# usb-can_v2_1.net
KiCad netlist of a schematic drawn in EAGLE
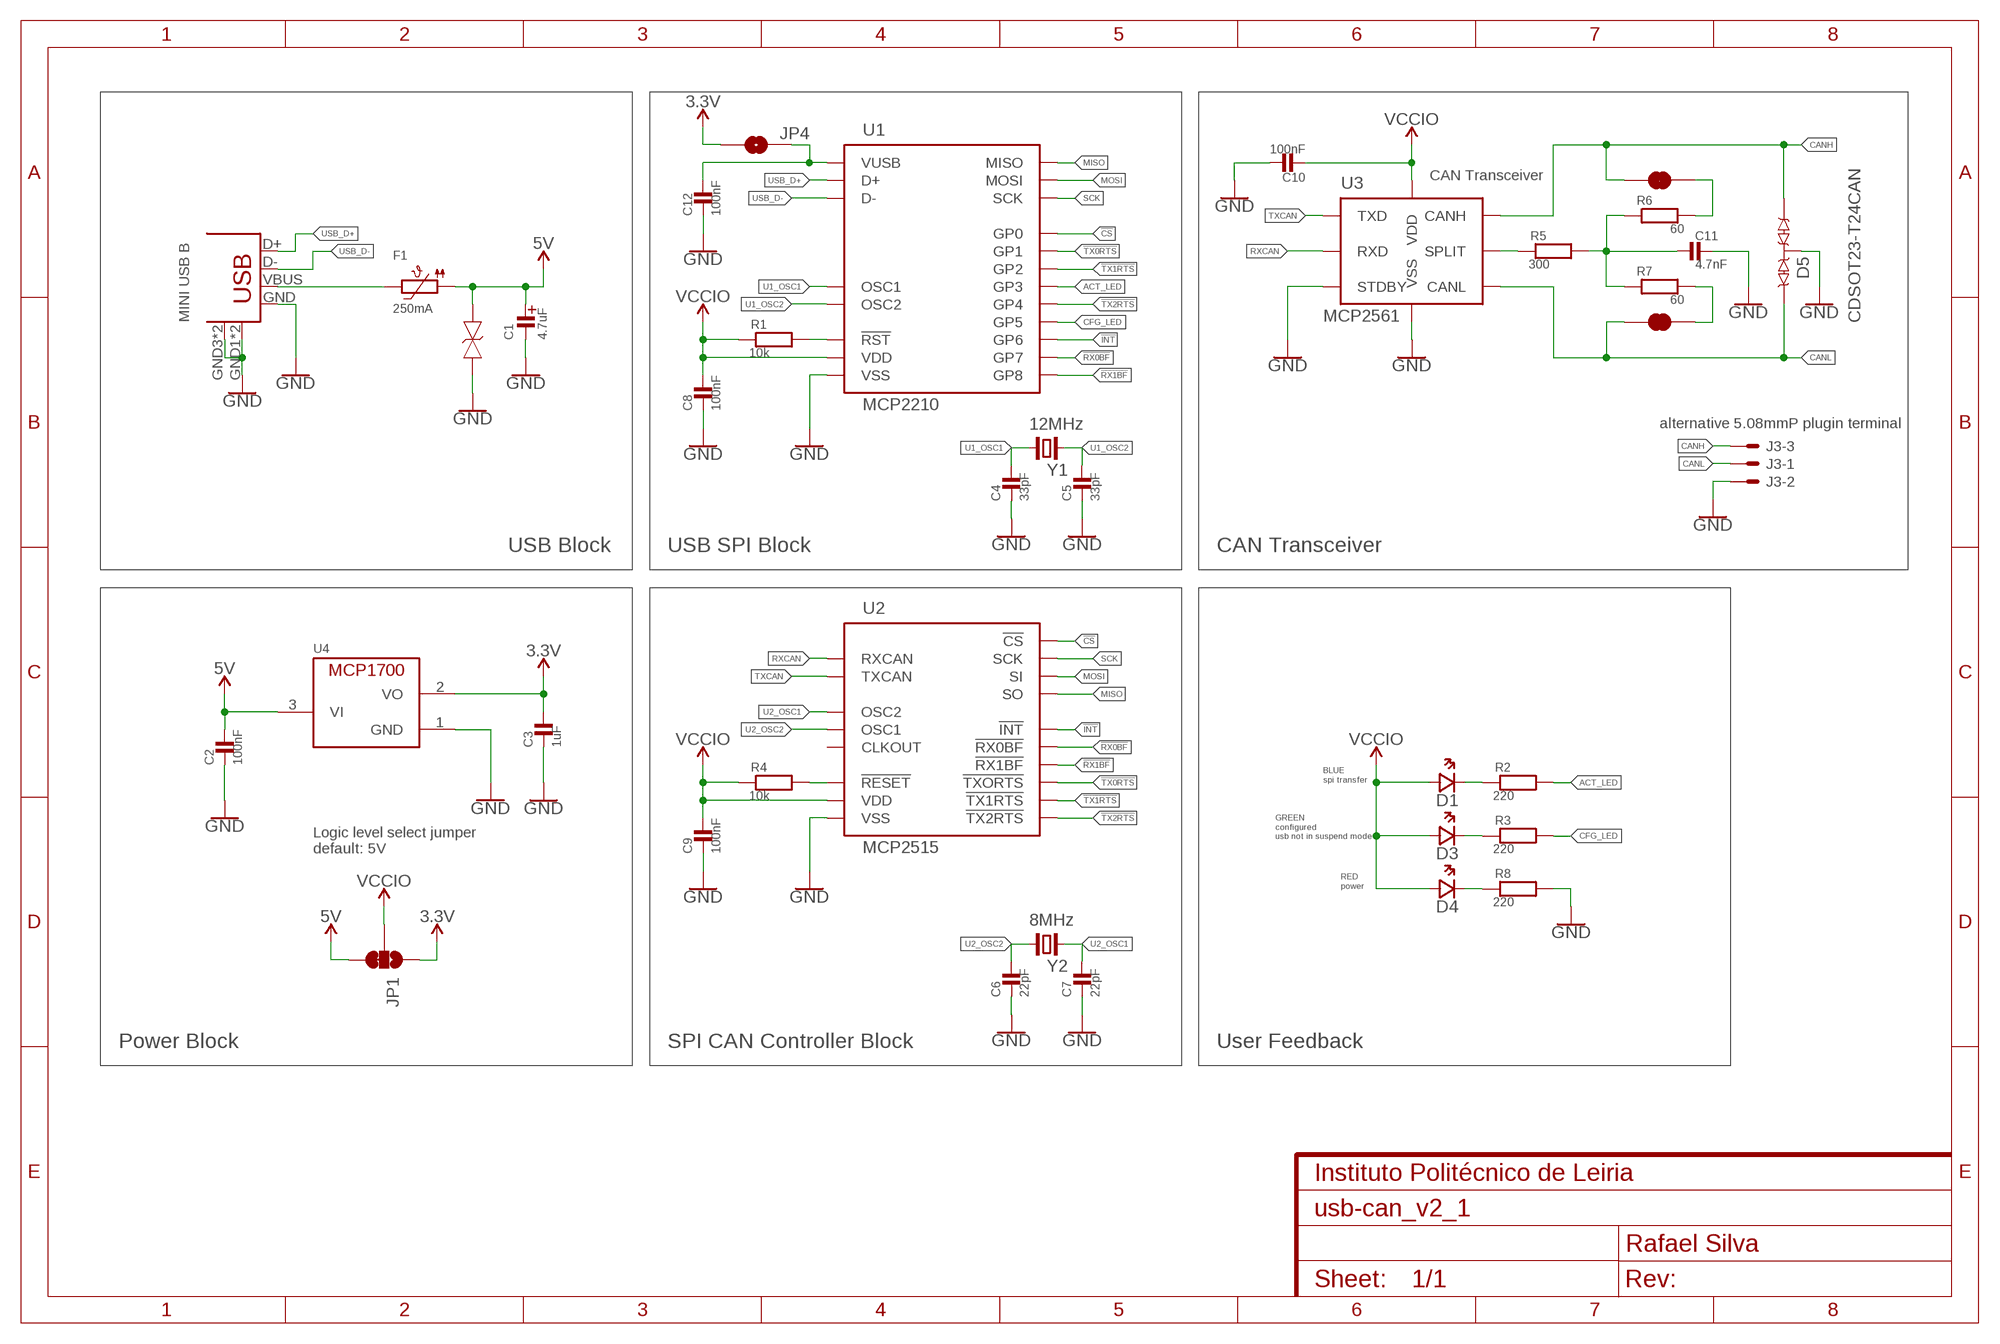
[diagram p0: schematic, sheet 1]

(export (version "E")
  (design (tool "Eeschema 10.0.6"))
  (components
    (comp (ref "C1")
      (value "4.7uF")
      (footprint "eagle-import:EIA3216")
      (libsource (lib "eagle-import") (part "CAPACITOR_TAN3216"))
    )
    (comp (ref "C2")
      (value "100nF")
      (footprint "eagle-import:0603_WAVE")
      (libsource (lib "eagle-import") (part "CAPACITOR_C0603"))
    )
    (comp (ref "C3")
      (value "1uF")
      (footprint "eagle-import:0603_WAVE")
      (libsource (lib "eagle-import") (part "CAPACITOR_C0603"))
    )
    (comp (ref "C4")
      (value "33pF")
      (footprint "eagle-import:0603_WAVE")
      (libsource (lib "eagle-import") (part "CAPACITOR_C0603"))
    )
    (comp (ref "C5")
      (value "33pF")
      (footprint "eagle-import:0603_WAVE")
      (libsource (lib "eagle-import") (part "CAPACITOR_C0603"))
    )
    (comp (ref "C6")
      (value "22pF")
      (footprint "eagle-import:0603_WAVE")
      (libsource (lib "eagle-import") (part "CAPACITOR_C0603"))
    )
    (comp (ref "C7")
      (value "22pF")
      (footprint "eagle-import:0603_WAVE")
      (libsource (lib "eagle-import") (part "CAPACITOR_C0603"))
    )
    (comp (ref "C8")
      (value "100nF")
      (footprint "eagle-import:0603_WAVE")
      (libsource (lib "eagle-import") (part "CAPACITOR_C0603"))
    )
    (comp (ref "C9")
      (value "100nF")
      (footprint "eagle-import:0603_WAVE")
      (libsource (lib "eagle-import") (part "CAPACITOR_C0603"))
    )
    (comp (ref "C10")
      (value "100nF")
      (footprint "eagle-import:0603_WAVE")
      (libsource (lib "eagle-import") (part "CAPACITOR_C0603"))
    )
    (comp (ref "C11")
      (value "4.7nF")
      (footprint "eagle-import:0603_WAVE")
      (libsource (lib "eagle-import") (part "CAPACITOR_C0603"))
    )
    (comp (ref "C12")
      (value "100nF")
      (footprint "eagle-import:0603_WAVE")
      (libsource (lib "eagle-import") (part "CAPACITOR_C0603"))
    )
    (comp (ref "D1")
      (value "Blue")
      (footprint "eagle-import:CHIPLED_0603")
      (libsource (lib "eagle-import") (part "LED0603"))
    )
    (comp (ref "D2")
      (value "PESD5V0S1BAF")
      (footprint "eagle-import:SOD323")
      (libsource (lib "eagle-import") (part "PESD5V0S1BAF"))
    )
    (comp (ref "D3")
      (value "Green")
      (footprint "eagle-import:CHIPLED_0603")
      (libsource (lib "eagle-import") (part "LED0603"))
    )
    (comp (ref "D4")
      (value "Red")
      (footprint "eagle-import:CHIPLED_0603")
      (libsource (lib "eagle-import") (part "LED0603"))
    )
    (comp (ref "D5")
      (value "CDSOT23-T24CAN")
      (footprint "eagle-import:SOT-23-3")
      (libsource (lib "eagle-import") (part "CDSOT23-T24CAN"))
    )
    (comp (ref "F1")
      (value "250mA")
      (footprint "eagle-import:_1206")
      (libsource (lib "eagle-import") (part "PTC1206"))
    )
    (comp (ref "J2")
      (value "USB_MINI_BMINIB")
      (footprint "eagle-import:USB-MINIB")
      (libsource (lib "eagle-import") (part "USB_MINI_BMINIB"))
    )
    (comp (ref "J3")
      (value "1X32EHGR")
      (footprint "eagle-import:2EHGR")
      (libsource (lib "eagle-import") (part "1X32EHGR"))
    )
    (comp (ref "JP1")
      (value "JUMPER-SMT_3_1-NC_TRACE_SILK")
      (footprint "eagle-import:SMT-JUMPER_3_1-NC_TRACE_SILK")
      (libsource (lib "eagle-import") (part "JUMPER-SMT_3_1-NC_TRACE_SILK"))
    )
    (comp (ref "JP2")
      (value "JUMPER-SMT_2_NC_TRACE_SILK")
      (footprint "eagle-import:SMT-JUMPER_2_NC_TRACE_SILK")
      (libsource (lib "eagle-import") (part "JUMPER-SMT_2_NC_TRACE_SILK"))
    )
    (comp (ref "JP3")
      (value "JUMPER-SMT_2_NC_TRACE_SILK")
      (footprint "eagle-import:SMT-JUMPER_2_NC_TRACE_SILK")
      (libsource (lib "eagle-import") (part "JUMPER-SMT_2_NC_TRACE_SILK"))
    )
    (comp (ref "JP4")
      (value "JUMPER-SMT_2_NO_SILK")
      (footprint "eagle-import:SMT-JUMPER_2_NO_SILK")
      (libsource (lib "eagle-import") (part "JUMPER-SMT_2_NO_SILK"))
    )
    (comp (ref "R1")
      (value "10k")
      (footprint "eagle-import:0603_WAVE")
      (libsource (lib "eagle-import") (part "RESISTOR0603"))
    )
    (comp (ref "R2")
      (value "220")
      (footprint "eagle-import:0603_WAVE")
      (libsource (lib "eagle-import") (part "RESISTOR0603"))
    )
    (comp (ref "R3")
      (value "220")
      (footprint "eagle-import:0603_WAVE")
      (libsource (lib "eagle-import") (part "RESISTOR0603"))
    )
    (comp (ref "R4")
      (value "10k")
      (footprint "eagle-import:0603_WAVE")
      (libsource (lib "eagle-import") (part "RESISTOR0603"))
    )
    (comp (ref "R5")
      (value "300")
      (footprint "eagle-import:0603_WAVE")
      (libsource (lib "eagle-import") (part "RESISTOR0603"))
    )
    (comp (ref "R6")
      (value "60")
      (footprint "eagle-import:0603_WAVE")
      (libsource (lib "eagle-import") (part "RESISTOR0603"))
    )
    (comp (ref "R7")
      (value "60")
      (footprint "eagle-import:0603_WAVE")
      (libsource (lib "eagle-import") (part "RESISTOR0603"))
    )
    (comp (ref "R8")
      (value "220")
      (footprint "eagle-import:0603_WAVE")
      (libsource (lib "eagle-import") (part "RESISTOR0603"))
    )
    (comp (ref "U1")
      (value "MCP2210")
      (footprint "eagle-import:SOIC-20_300MIL")
      (libsource (lib "eagle-import") (part "MCP2210"))
    )
    (comp (ref "U2")
      (value "MCP2515")
      (footprint "eagle-import:SOIC-18_300MIL")
      (libsource (lib "eagle-import") (part "MCP2515"))
    )
    (comp (ref "U3")
      (value "MCP2561")
      (footprint "eagle-import:SOIC_8")
      (libsource (lib "eagle-import") (part "MCP2561"))
    )
    (comp (ref "U4")
      (value "250mA")
      (footprint "eagle-import:SOT-23")
      (libsource (lib "eagle-import") (part "MCP1700T-3302TT"))
    )
    (comp (ref "Y1")
      (value "12MHz")
      (footprint "eagle-import:2-SMD-5X3")
      (libsource (lib "eagle-import") (part "CRYSTALNX5032GA"))
    )
    (comp (ref "Y2")
      (value "8MHz")
      (footprint "eagle-import:2-SMD-5X3")
      (libsource (lib "eagle-import") (part "CRYSTALNX5032GA"))
    )
  )
  (nets
    (net (code "1") (name "/~{CS}") (class "Default")
      (node (ref "U1") (pin "P$5") (pinfunction "GP0_P$5") (pintype "bidirectional"))
      (node (ref "U2") (pin "P$16") (pinfunction "~{CS}_P$16") (pintype "bidirectional"))
    )
    (net (code "2") (name "/~{INT}") (class "Default")
      (node (ref "U1") (pin "P$14") (pinfunction "GP6_P$14") (pintype "bidirectional"))
      (node (ref "U2") (pin "P$12") (pinfunction "~{INT}_P$12") (pintype "bidirectional"))
    )
    (net (code "3") (name "/~{RX0BF}") (class "Default")
      (node (ref "U1") (pin "P$15") (pinfunction "GP7_P$15") (pintype "bidirectional"))
      (node (ref "U2") (pin "P$11") (pinfunction "~{RX0BF}_P$11") (pintype "bidirectional"))
    )
    (net (code "4") (name "/~{RX1BF}") (class "Default")
      (node (ref "U1") (pin "P$16") (pinfunction "GP8_P$16") (pintype "bidirectional"))
      (node (ref "U2") (pin "P$10") (pinfunction "~{RX1BF}_P$10") (pintype "bidirectional"))
    )
    (net (code "5") (name "/~{TX0RTS}") (class "Default")
      (node (ref "U1") (pin "P$6") (pinfunction "GP1_P$6") (pintype "bidirectional"))
      (node (ref "U2") (pin "P$4") (pinfunction "~{TXORTS}_P$4") (pintype "bidirectional"))
    )
    (net (code "6") (name "/~{TX1RTS}") (class "Default")
      (node (ref "U1") (pin "P$7") (pinfunction "GP2_P$7") (pintype "bidirectional"))
      (node (ref "U2") (pin "P$5") (pinfunction "~{TX1RTS}_P$5") (pintype "bidirectional"))
    )
    (net (code "7") (name "/~{TX2RTS}") (class "Default")
      (node (ref "U1") (pin "P$10") (pinfunction "GP4_P$10") (pintype "bidirectional"))
      (node (ref "U2") (pin "P$6") (pinfunction "~{TX2RTS}_P$6") (pintype "bidirectional"))
    )
    (net (code "8") (name "3.3V") (class "Default")
      (node (ref "C3") (pin "P$1") (pinfunction "P$1_P$1") (pintype "bidirectional"))
      (node (ref "JP1") (pin "1") (pinfunction "1_1") (pintype "passive"))
      (node (ref "JP4") (pin "2") (pinfunction "2_2") (pintype "passive"))
      (node (ref "U4") (pin "2") (pinfunction "VO_2") (pintype "bidirectional"))
    )
    (net (code "9") (name "5V") (class "Default")
      (node (ref "C1") (pin "+") (pinfunction "AN_+") (pintype "bidirectional"))
      (node (ref "C2") (pin "P$1") (pinfunction "P$1_P$1") (pintype "bidirectional"))
      (node (ref "D2") (pin "P$1") (pinfunction "P$1_P$1") (pintype "bidirectional"))
      (node (ref "F1") (pin "1") (pinfunction "1_1") (pintype "passive"))
      (node (ref "JP1") (pin "3") (pinfunction "3_3") (pintype "passive"))
      (node (ref "U4") (pin "3") (pinfunction "VI_3") (pintype "bidirectional"))
    )
    (net (code "10") (name "ACT_LED") (class "Default")
      (node (ref "R2") (pin "P$2") (pinfunction "P$2_P$2") (pintype "bidirectional"))
      (node (ref "U1") (pin "P$8") (pinfunction "GP3_P$8") (pintype "bidirectional"))
    )
    (net (code "11") (name "CANH") (class "Default")
      (node (ref "D5") (pin "P$2") (pinfunction "2_P$2") (pintype "bidirectional"))
      (node (ref "J3") (pin "P$3") (pinfunction "S_P$3") (pintype "passive"))
      (node (ref "JP3") (pin "2") (pinfunction "2_2") (pintype "passive"))
      (node (ref "U3") (pin "P$7") (pinfunction "CANH_P$7") (pintype "bidirectional"))
    )
    (net (code "12") (name "CANL") (class "Default")
      (node (ref "D5") (pin "P$1") (pinfunction "1_P$1") (pintype "bidirectional"))
      (node (ref "J3") (pin "P$1") (pinfunction "S_P$1") (pintype "passive"))
      (node (ref "JP2") (pin "2") (pinfunction "2_2") (pintype "passive"))
      (node (ref "U3") (pin "P$6") (pinfunction "CANL_P$6") (pintype "bidirectional"))
    )
    (net (code "13") (name "CFG_LED") (class "Default")
      (node (ref "R3") (pin "P$2") (pinfunction "P$2_P$2") (pintype "bidirectional"))
      (node (ref "U1") (pin "P$12") (pinfunction "GP5_P$12") (pintype "bidirectional"))
    )
    (net (code "14") (name "GND") (class "Default")
      (node (ref "C1") (pin "-") (pinfunction "CA_-") (pintype "bidirectional"))
      (node (ref "C10") (pin "P$1") (pinfunction "P$1_P$1") (pintype "bidirectional"))
      (node (ref "C11") (pin "P$1") (pinfunction "P$1_P$1") (pintype "bidirectional"))
      (node (ref "C12") (pin "P$2") (pinfunction "P$2_P$2") (pintype "bidirectional"))
      (node (ref "C2") (pin "P$2") (pinfunction "P$2_P$2") (pintype "bidirectional"))
      (node (ref "C3") (pin "P$2") (pinfunction "P$2_P$2") (pintype "bidirectional"))
      (node (ref "C4") (pin "P$2") (pinfunction "P$2_P$2") (pintype "bidirectional"))
      (node (ref "C5") (pin "P$2") (pinfunction "P$2_P$2") (pintype "bidirectional"))
      (node (ref "C6") (pin "P$2") (pinfunction "P$2_P$2") (pintype "bidirectional"))
      (node (ref "C7") (pin "P$2") (pinfunction "P$2_P$2") (pintype "bidirectional"))
      (node (ref "C8") (pin "P$2") (pinfunction "P$2_P$2") (pintype "bidirectional"))
      (node (ref "C9") (pin "P$2") (pinfunction "P$2_P$2") (pintype "bidirectional"))
      (node (ref "D2") (pin "P$2") (pinfunction "P$2_P$2") (pintype "bidirectional"))
      (node (ref "D5") (pin "P$3") (pinfunction "3_P$3") (pintype "bidirectional"))
      (node (ref "J2") (pin "GND") (pinfunction "GND_GND") (pintype "bidirectional"))
      (node (ref "J2") (pin "GND1") (pinfunction "P$1_GND1") (pintype "bidirectional"))
      (node (ref "J2") (pin "GND2") (pinfunction "P$1_GND2") (pintype "bidirectional"))
      (node (ref "J2") (pin "GND3") (pinfunction "P$2_GND3") (pintype "bidirectional"))
      (node (ref "J2") (pin "GND4") (pinfunction "P$2_GND4") (pintype "bidirectional"))
      (node (ref "J3") (pin "P$2") (pinfunction "S_P$2") (pintype "passive"))
      (node (ref "R8") (pin "P$2") (pinfunction "P$2_P$2") (pintype "bidirectional"))
      (node (ref "U1") (pin "P$20") (pinfunction "VSS_P$20") (pintype "bidirectional"))
      (node (ref "U2") (pin "P$9") (pinfunction "VSS_P$9") (pintype "bidirectional"))
      (node (ref "U3") (pin "P$2") (pinfunction "VSS_P$2") (pintype "bidirectional"))
      (node (ref "U3") (pin "P$8") (pinfunction "STDBY_P$8") (pintype "bidirectional"))
      (node (ref "U4") (pin "1") (pinfunction "GND_1") (pintype "bidirectional"))
    )
    (net (code "15") (name "MISO") (class "Default")
      (node (ref "U1") (pin "P$13") (pinfunction "MISO_P$13") (pintype "bidirectional"))
      (node (ref "U2") (pin "P$15") (pinfunction "SO_P$15") (pintype "bidirectional"))
    )
    (net (code "16") (name "MOSI") (class "Default")
      (node (ref "U1") (pin "P$9") (pinfunction "MOSI_P$9") (pintype "bidirectional"))
      (node (ref "U2") (pin "P$14") (pinfunction "SI_P$14") (pintype "bidirectional"))
    )
    (net (code "17") (name "Net-(C11-PadP$2)") (class "Default")
      (node (ref "C11") (pin "P$2") (pinfunction "P$2_P$2") (pintype "bidirectional"))
      (node (ref "R5") (pin "P$2") (pinfunction "P$2_P$2") (pintype "bidirectional"))
      (node (ref "R6") (pin "P$1") (pinfunction "P$1_P$1") (pintype "bidirectional"))
      (node (ref "R7") (pin "P$1") (pinfunction "P$1_P$1") (pintype "bidirectional"))
    )
    (net (code "18") (name "Net-(D1-CA)") (class "Default")
      (node (ref "D1") (pin "C") (pinfunction "CA_C") (pintype "bidirectional"))
      (node (ref "R2") (pin "P$1") (pinfunction "P$1_P$1") (pintype "bidirectional"))
    )
    (net (code "19") (name "Net-(D3-CA)") (class "Default")
      (node (ref "D3") (pin "C") (pinfunction "CA_C") (pintype "bidirectional"))
      (node (ref "R3") (pin "P$1") (pinfunction "P$1_P$1") (pintype "bidirectional"))
    )
    (net (code "20") (name "Net-(D4-CA)") (class "Default")
      (node (ref "D4") (pin "C") (pinfunction "CA_C") (pintype "bidirectional"))
      (node (ref "R8") (pin "P$1") (pinfunction "P$1_P$1") (pintype "bidirectional"))
    )
    (net (code "21") (name "Net-(F1-Pad2)") (class "Default")
      (node (ref "F1") (pin "2") (pinfunction "2_2") (pintype "passive"))
      (node (ref "J2") (pin "VBUS") (pinfunction "VBUS_VBUS") (pintype "bidirectional"))
    )
    (net (code "22") (name "Net-(JP2-Pad1)") (class "Default")
      (node (ref "JP2") (pin "1") (pinfunction "1_1") (pintype "passive"))
      (node (ref "R7") (pin "P$2") (pinfunction "P$2_P$2") (pintype "bidirectional"))
    )
    (net (code "23") (name "Net-(JP3-Pad1)") (class "Default")
      (node (ref "JP3") (pin "1") (pinfunction "1_1") (pintype "passive"))
      (node (ref "R6") (pin "P$2") (pinfunction "P$2_P$2") (pintype "bidirectional"))
    )
    (net (code "24") (name "Net-(U1-VUSB)") (class "Default")
      (node (ref "C12") (pin "P$1") (pinfunction "P$1_P$1") (pintype "bidirectional"))
      (node (ref "JP4") (pin "1") (pinfunction "1_1") (pintype "passive"))
      (node (ref "U1") (pin "P$17") (pinfunction "VUSB_P$17") (pintype "bidirectional"))
    )
    (net (code "25") (name "Net-(U1-~{RST})") (class "Default")
      (node (ref "R1") (pin "P$2") (pinfunction "P$2_P$2") (pintype "bidirectional"))
      (node (ref "U1") (pin "P$4") (pinfunction "~{RST}_P$4") (pintype "bidirectional"))
    )
    (net (code "26") (name "Net-(U2-~{RESET})") (class "Default")
      (node (ref "R4") (pin "P$2") (pinfunction "P$2_P$2") (pintype "bidirectional"))
      (node (ref "U2") (pin "P$17") (pinfunction "~{RESET}_P$17") (pintype "bidirectional"))
    )
    (net (code "27") (name "Net-(U3-SPLIT)") (class "Default")
      (node (ref "R5") (pin "P$1") (pinfunction "P$1_P$1") (pintype "bidirectional"))
      (node (ref "U3") (pin "P$5") (pinfunction "SPLIT_P$5") (pintype "power_in"))
    )
    (net (code "28") (name "RXCAN") (class "Default")
      (node (ref "U2") (pin "P$2") (pinfunction "RXCAN_P$2") (pintype "bidirectional"))
      (node (ref "U3") (pin "P$4") (pinfunction "RXD_P$4") (pintype "bidirectional"))
    )
    (net (code "29") (name "SCK") (class "Default")
      (node (ref "U1") (pin "P$11") (pinfunction "SCK_P$11") (pintype "bidirectional"))
      (node (ref "U2") (pin "P$13") (pinfunction "SCK_P$13") (pintype "bidirectional"))
    )
    (net (code "30") (name "TXCAN") (class "Default")
      (node (ref "U2") (pin "P$1") (pinfunction "TXCAN_P$1") (pintype "bidirectional"))
      (node (ref "U3") (pin "P$1") (pinfunction "TXD_P$1") (pintype "bidirectional"))
    )
    (net (code "31") (name "U1_OSC1") (class "Default")
      (node (ref "C4") (pin "P$1") (pinfunction "P$1_P$1") (pintype "bidirectional"))
      (node (ref "U1") (pin "P$2") (pinfunction "OSC1_P$2") (pintype "bidirectional"))
      (node (ref "Y1") (pin "1") (pinfunction "1_1") (pintype "passive"))
    )
    (net (code "32") (name "U1_OSC2") (class "Default")
      (node (ref "C5") (pin "P$1") (pinfunction "P$1_P$1") (pintype "bidirectional"))
      (node (ref "U1") (pin "P$3") (pinfunction "OSC2_P$3") (pintype "bidirectional"))
      (node (ref "Y1") (pin "2") (pinfunction "2_2") (pintype "passive"))
    )
    (net (code "33") (name "U2_OSC1") (class "Default")
      (node (ref "C7") (pin "P$1") (pinfunction "P$1_P$1") (pintype "bidirectional"))
      (node (ref "U2") (pin "P$7") (pinfunction "OSC2_P$7") (pintype "bidirectional"))
      (node (ref "Y2") (pin "2") (pinfunction "2_2") (pintype "passive"))
    )
    (net (code "34") (name "U2_OSC2") (class "Default")
      (node (ref "C6") (pin "P$1") (pinfunction "P$1_P$1") (pintype "bidirectional"))
      (node (ref "U2") (pin "P$8") (pinfunction "OSC1_P$8") (pintype "bidirectional"))
      (node (ref "Y2") (pin "1") (pinfunction "1_1") (pintype "passive"))
    )
    (net (code "35") (name "USB_D+") (class "Default")
      (node (ref "J2") (pin "D+") (pinfunction "D+_D+") (pintype "bidirectional"))
      (node (ref "U1") (pin "P$19") (pinfunction "D+_P$19") (pintype "bidirectional"))
    )
    (net (code "36") (name "USB_D-") (class "Default")
      (node (ref "J2") (pin "D-") (pinfunction "D-_D-") (pintype "bidirectional"))
      (node (ref "U1") (pin "P$18") (pinfunction "D-_P$18") (pintype "bidirectional"))
    )
    (net (code "37") (name "VCCIO") (class "Default")
      (node (ref "C10") (pin "P$2") (pinfunction "P$2_P$2") (pintype "bidirectional"))
      (node (ref "C8") (pin "P$1") (pinfunction "P$1_P$1") (pintype "bidirectional"))
      (node (ref "C9") (pin "P$1") (pinfunction "P$1_P$1") (pintype "bidirectional"))
      (node (ref "D1") (pin "A") (pinfunction "AN_A") (pintype "bidirectional"))
      (node (ref "D3") (pin "A") (pinfunction "AN_A") (pintype "bidirectional"))
      (node (ref "D4") (pin "A") (pinfunction "AN_A") (pintype "bidirectional"))
      (node (ref "JP1") (pin "2") (pinfunction "2_2") (pintype "passive"))
      (node (ref "R1") (pin "P$1") (pinfunction "P$1_P$1") (pintype "bidirectional"))
      (node (ref "R4") (pin "P$1") (pinfunction "P$1_P$1") (pintype "bidirectional"))
      (node (ref "U1") (pin "P$1") (pinfunction "VDD_P$1") (pintype "bidirectional"))
      (node (ref "U2") (pin "P$18") (pinfunction "VDD_P$18") (pintype "bidirectional"))
      (node (ref "U3") (pin "P$3") (pinfunction "VDD_P$3") (pintype "bidirectional"))
    )
    (net (code "38") (name "unconnected-(U2-CLKOUT-PadP$3)") (class "Default")
      (node (ref "U2") (pin "P$3") (pinfunction "CLKOUT_P$3") (pintype "bidirectional"))
    )
  )
)
